# SSD1963_drier.net
KiCad netlist of a schematic drawn in EAGLE
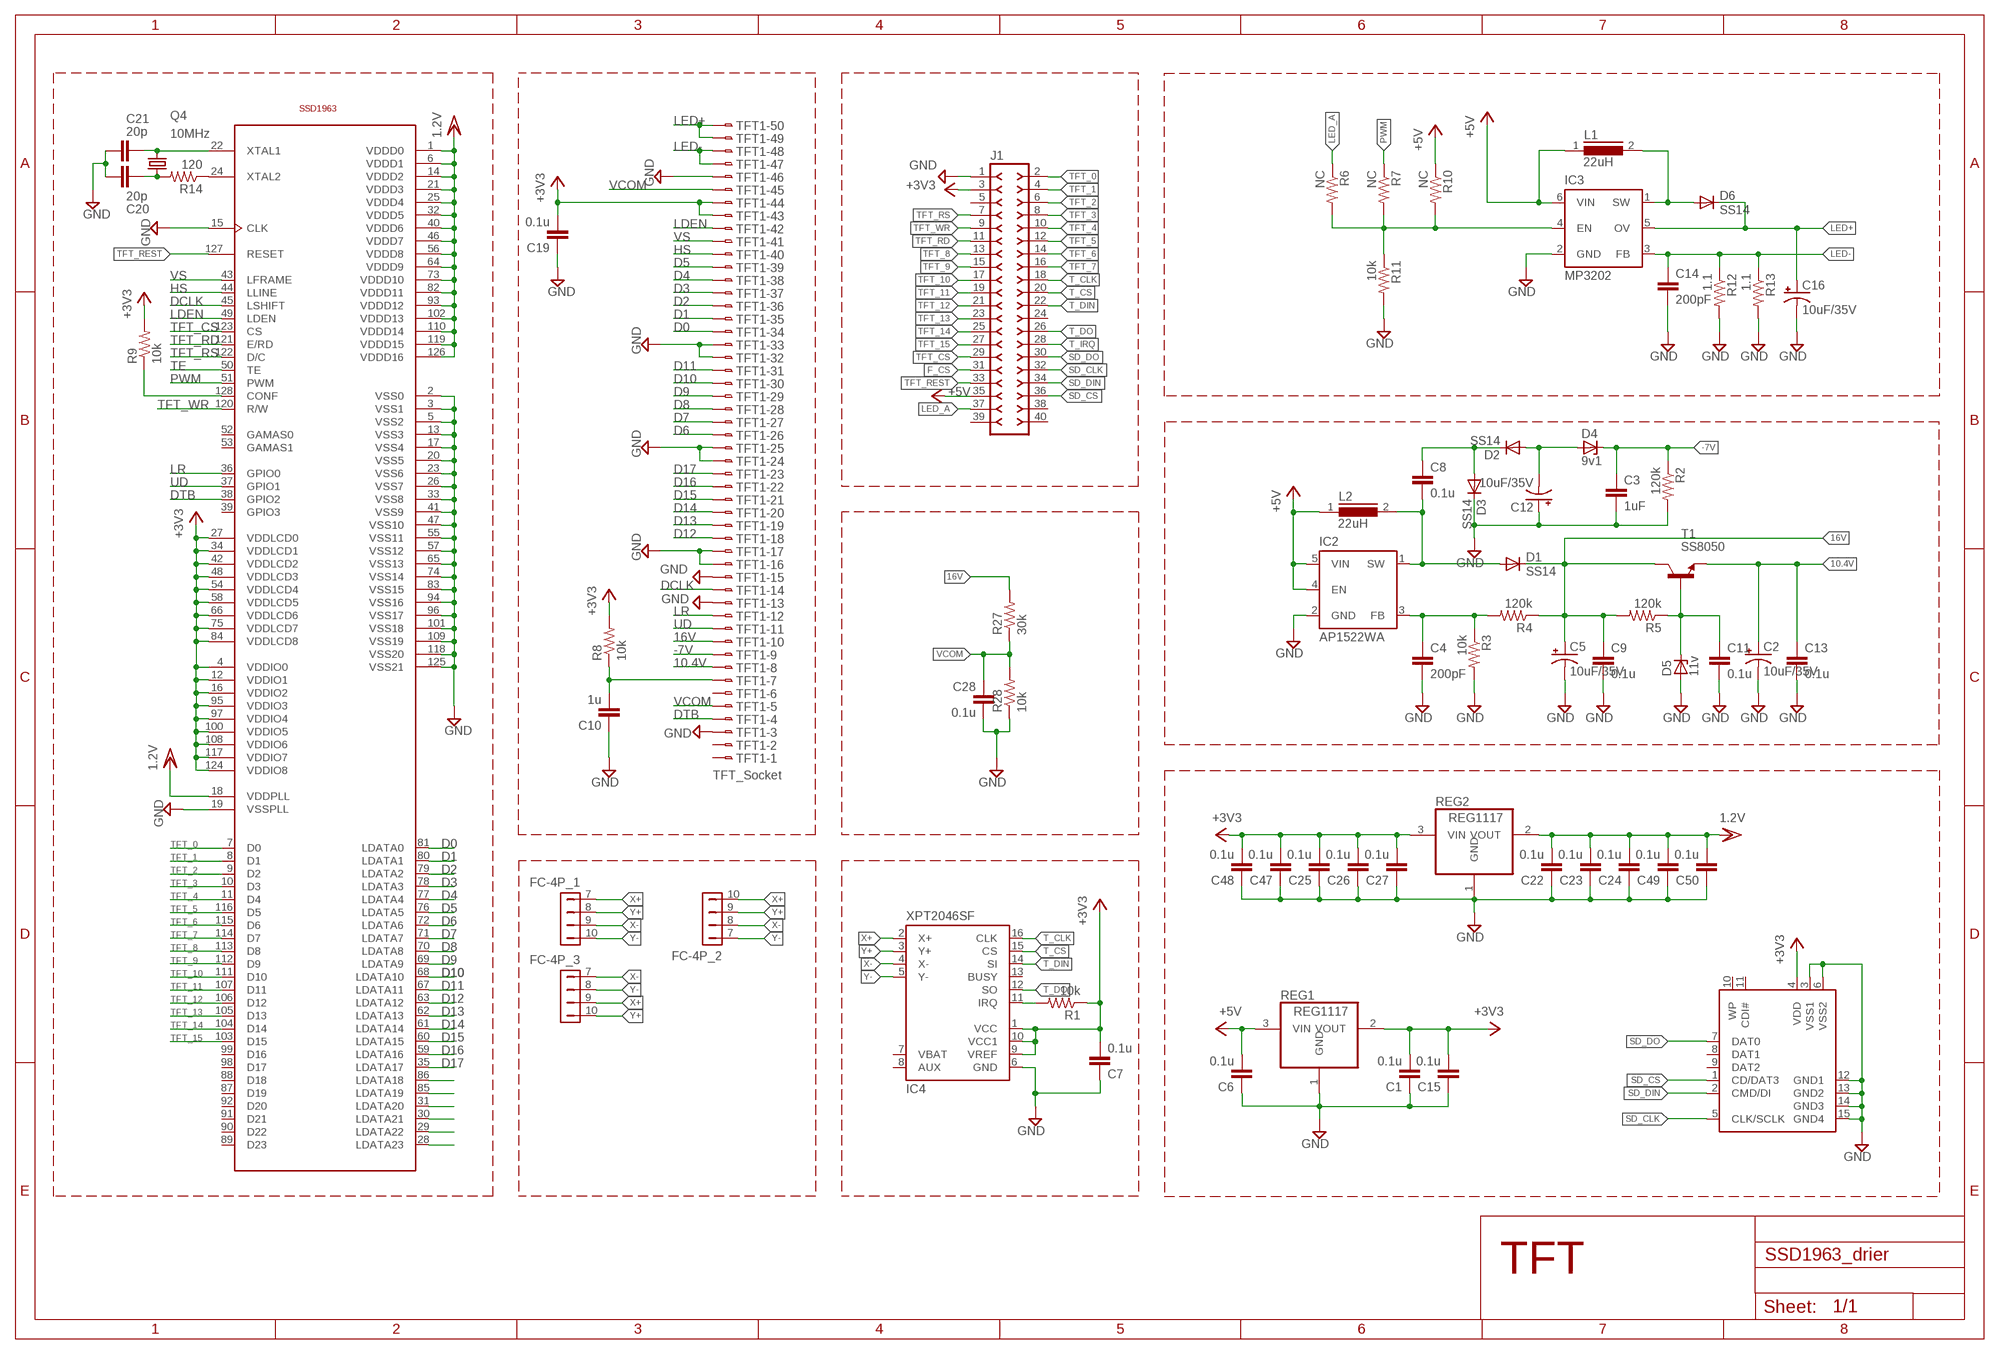
[diagram p0: schematic, sheet 1]

(export (version "E")
  (design (tool "Eeschema 10.0.6"))
  (components
    (comp (ref "C1")
      (value "0.1u")
      (footprint "eagle-import:C0805")
      (libsource (lib "eagle-import") (part "C-EUC0805"))
    )
    (comp (ref "C2")
      (value "10uF/35V")
      (footprint "eagle-import:B_3528-21R")
      (libsource (lib "eagle-import") (part "CPOL-USB/3528-21R"))
    )
    (comp (ref "C3")
      (value "1uF")
      (footprint "eagle-import:C0805")
      (libsource (lib "eagle-import") (part "C-EUC0805"))
    )
    (comp (ref "C4")
      (value "200pF")
      (footprint "eagle-import:C0805")
      (libsource (lib "eagle-import") (part "C-EUC0805"))
    )
    (comp (ref "C5")
      (value "10uF/35V")
      (footprint "eagle-import:B_3528-21R")
      (libsource (lib "eagle-import") (part "CPOL-USB/3528-21R"))
    )
    (comp (ref "C6")
      (value "0.1u")
      (footprint "eagle-import:C0805")
      (libsource (lib "eagle-import") (part "C-EUC0805"))
    )
    (comp (ref "C7")
      (value "0.1u")
      (footprint "eagle-import:C0805")
      (libsource (lib "eagle-import") (part "C-EUC0805"))
    )
    (comp (ref "C8")
      (value "0.1u")
      (footprint "eagle-import:C0805")
      (libsource (lib "eagle-import") (part "C-EUC0805"))
    )
    (comp (ref "C9")
      (value "0.1u")
      (footprint "eagle-import:C0805")
      (libsource (lib "eagle-import") (part "C-EUC0805"))
    )
    (comp (ref "C10")
      (value "1u")
      (footprint "eagle-import:C0805")
      (libsource (lib "eagle-import") (part "C-EUC0805"))
    )
    (comp (ref "C11")
      (value "0.1u")
      (footprint "eagle-import:C0805")
      (libsource (lib "eagle-import") (part "C-EUC0805"))
    )
    (comp (ref "C12")
      (value "10uF/35V")
      (footprint "eagle-import:B_3528-21R")
      (libsource (lib "eagle-import") (part "CPOL-USB/3528-21R"))
    )
    (comp (ref "C13")
      (value "0.1u")
      (footprint "eagle-import:C0805")
      (libsource (lib "eagle-import") (part "C-EUC0805"))
    )
    (comp (ref "C14")
      (value "200pF")
      (footprint "eagle-import:C0805")
      (libsource (lib "eagle-import") (part "C-EUC0805"))
    )
    (comp (ref "C15")
      (value "0.1u")
      (footprint "eagle-import:C0805")
      (libsource (lib "eagle-import") (part "C-EUC0805"))
    )
    (comp (ref "C16")
      (value "10uF/35V")
      (footprint "eagle-import:B_3528-21R")
      (libsource (lib "eagle-import") (part "CPOL-USB/3528-21R"))
    )
    (comp (ref "C19")
      (value "0.1u")
      (footprint "eagle-import:C0805")
      (libsource (lib "eagle-import") (part "C-EUC0805"))
    )
    (comp (ref "C20")
      (value "20p")
      (footprint "eagle-import:C0805")
      (libsource (lib "eagle-import") (part "C-EUC0805"))
    )
    (comp (ref "C21")
      (value "20p")
      (footprint "eagle-import:C0805")
      (libsource (lib "eagle-import") (part "C-EUC0805"))
    )
    (comp (ref "C22")
      (value "0.1u")
      (footprint "eagle-import:C0805")
      (libsource (lib "eagle-import") (part "C-EUC0805"))
    )
    (comp (ref "C23")
      (value "0.1u")
      (footprint "eagle-import:C0805")
      (libsource (lib "eagle-import") (part "C-EUC0805"))
    )
    (comp (ref "C24")
      (value "0.1u")
      (footprint "eagle-import:C0805")
      (libsource (lib "eagle-import") (part "C-EUC0805"))
    )
    (comp (ref "C25")
      (value "0.1u")
      (footprint "eagle-import:C0805")
      (libsource (lib "eagle-import") (part "C-EUC0805"))
    )
    (comp (ref "C26")
      (value "0.1u")
      (footprint "eagle-import:C0805")
      (libsource (lib "eagle-import") (part "C-EUC0805"))
    )
    (comp (ref "C27")
      (value "0.1u")
      (footprint "eagle-import:C0805")
      (libsource (lib "eagle-import") (part "C-EUC0805"))
    )
    (comp (ref "C28")
      (value "0.1u")
      (footprint "eagle-import:C0805")
      (libsource (lib "eagle-import") (part "C-EUC0805"))
    )
    (comp (ref "C47")
      (value "0.1u")
      (footprint "eagle-import:C0805")
      (libsource (lib "eagle-import") (part "C-EUC0805"))
    )
    (comp (ref "C48")
      (value "0.1u")
      (footprint "eagle-import:C0805")
      (libsource (lib "eagle-import") (part "C-EUC0805"))
    )
    (comp (ref "C49")
      (value "0.1u")
      (footprint "eagle-import:C0805")
      (libsource (lib "eagle-import") (part "C-EUC0805"))
    )
    (comp (ref "C50")
      (value "0.1u")
      (footprint "eagle-import:C0805")
      (libsource (lib "eagle-import") (part "C-EUC0805"))
    )
    (comp (ref "D1")
      (value "SS14")
      (footprint "eagle-import:DO214AC")
      (libsource (lib "eagle-import") (part "DIODE-DO214AC"))
    )
    (comp (ref "D2")
      (value "SS14")
      (footprint "eagle-import:DO214AC")
      (libsource (lib "eagle-import") (part "DIODE-DO214AC"))
    )
    (comp (ref "D3")
      (value "SS14")
      (footprint "eagle-import:DO214AC")
      (libsource (lib "eagle-import") (part "DIODE-DO214AC"))
    )
    (comp (ref "D4")
      (value "9v1")
      (footprint "eagle-import:SOD80C")
      (libsource (lib "eagle-import") (part "ZENER-DIODESOD80C"))
    )
    (comp (ref "D5")
      (value "11v")
      (footprint "eagle-import:SOD80C")
      (libsource (lib "eagle-import") (part "ZENER-DIODESOD80C"))
    )
    (comp (ref "D6")
      (value "SS14")
      (footprint "eagle-import:DO214AC")
      (libsource (lib "eagle-import") (part "DIODE-DO214AC"))
    )
    (comp (ref "FC-4P_1")
      (value "FH12-04S-1S")
      (footprint "eagle-import:FH12-4S-1SH")
      (libsource (lib "eagle-import") (part "FH12-04S-1S"))
    )
    (comp (ref "FC-4P_2")
      (value "FH12-04S-1S")
      (footprint "eagle-import:FH12-4S-1SH")
      (libsource (lib "eagle-import") (part "FH12-04S-1S"))
    )
    (comp (ref "FC-4P_3")
      (value "FH12-04S-1S")
      (footprint "eagle-import:FH12-4S-1SH")
      (libsource (lib "eagle-import") (part "FH12-04S-1S"))
    )
    (comp (ref "IC1")
      (value "SSD1963LQFP")
      (footprint "eagle-import:LQFP128")
      (libsource (lib "eagle-import") (part "SSD1963LQFP"))
    )
    (comp (ref "IC2")
      (value "AP1522WA")
      (footprint "eagle-import:SOT23-5L")
      (libsource (lib "eagle-import") (part "AP1522WA"))
    )
    (comp (ref "IC3")
      (value "MP3202")
      (footprint "eagle-import:SOT23-6L")
      (libsource (lib "eagle-import") (part "MP3202"))
    )
    (comp (ref "IC4")
      (value "XPT2046SF")
      (footprint "eagle-import:TSSOP16L")
      (libsource (lib "eagle-import") (part "XPT2046SF"))
    )
    (comp (ref "J1")
      (value "F-2X20-SF-100")
      (footprint "eagle-import:SF-100-2X20")
      (libsource (lib "eagle-import") (part "F-2X20-SF-100"))
    )
    (comp (ref "L1")
      (value "22uH")
      (footprint "eagle-import:DR74")
      (libsource (lib "eagle-import") (part "DR74"))
    )
    (comp (ref "L2")
      (value "22uH")
      (footprint "eagle-import:DR74")
      (libsource (lib "eagle-import") (part "DR74"))
    )
    (comp (ref "Q4")
      (value "10MHz")
      (footprint "eagle-import:HC49UP")
      (fields (field (name "OC_FARNELL") "unknown") (field (name "OC_NEWARK") "unknown"))
      (libsource (lib "eagle-import") (part "CRYSTALHC49UP"))
    )
    (comp (ref "R1")
      (value "10k")
      (footprint "eagle-import:R0805")
      (libsource (lib "eagle-import") (part "R-US_R0805"))
    )
    (comp (ref "R2")
      (value "120k")
      (footprint "eagle-import:R0805")
      (libsource (lib "eagle-import") (part "R-US_R0805"))
    )
    (comp (ref "R3")
      (value "10k")
      (footprint "eagle-import:R0805")
      (libsource (lib "eagle-import") (part "R-US_R0805"))
    )
    (comp (ref "R4")
      (value "120k")
      (footprint "eagle-import:R0805")
      (libsource (lib "eagle-import") (part "R-US_R0805"))
    )
    (comp (ref "R5")
      (value "120k")
      (footprint "eagle-import:R0805")
      (libsource (lib "eagle-import") (part "R-US_R0805"))
    )
    (comp (ref "R6")
      (value "NC")
      (footprint "eagle-import:R0805")
      (libsource (lib "eagle-import") (part "R-US_R0805"))
    )
    (comp (ref "R7")
      (value "NC")
      (footprint "eagle-import:R0805")
      (libsource (lib "eagle-import") (part "R-US_R0805"))
    )
    (comp (ref "R8")
      (value "10k")
      (footprint "eagle-import:M0805")
      (libsource (lib "eagle-import") (part "resistor_R-US_M0805"))
    )
    (comp (ref "R9")
      (value "10k")
      (footprint "eagle-import:M0805")
      (libsource (lib "eagle-import") (part "resistor_R-US_M0805"))
    )
    (comp (ref "R10")
      (value "NC")
      (footprint "eagle-import:R0805")
      (libsource (lib "eagle-import") (part "R-US_R0805"))
    )
    (comp (ref "R11")
      (value "10k")
      (footprint "eagle-import:R0805")
      (libsource (lib "eagle-import") (part "R-US_R0805"))
    )
    (comp (ref "R12")
      (value "1.1")
      (footprint "eagle-import:R0805")
      (libsource (lib "eagle-import") (part "R-US_R0805"))
    )
    (comp (ref "R13")
      (value "1.1")
      (footprint "eagle-import:R0805")
      (libsource (lib "eagle-import") (part "R-US_R0805"))
    )
    (comp (ref "R14")
      (value "120")
      (footprint "eagle-import:M0805")
      (libsource (lib "eagle-import") (part "resistor_R-US_M0805"))
    )
    (comp (ref "R27")
      (value "30k")
      (footprint "eagle-import:M0805")
      (libsource (lib "eagle-import") (part "resistor_R-US_M0805"))
    )
    (comp (ref "R28")
      (value "10k")
      (footprint "eagle-import:M0805")
      (libsource (lib "eagle-import") (part "resistor_R-US_M0805"))
    )
    (comp (ref "REG1")
      (value "REG1117")
      (footprint "eagle-import:SOT223")
      (fields
        (field (name "MPN") "REG1117")
        (field (name "OC_FARNELL") "1097566")
        (field (name "OC_NEWARK") "14P6981")
      )
      (libsource (lib "eagle-import") (part "REG1117"))
    )
    (comp (ref "REG2")
      (value "REG1117")
      (footprint "eagle-import:SOT223")
      (fields
        (field (name "MPN") "REG1117")
        (field (name "OC_FARNELL") "1097566")
        (field (name "OC_NEWARK") "14P6981")
      )
      (libsource (lib "eagle-import") (part "REG1117"))
    )
    (comp (ref "SOC_1")
      (value "MMC/SD")
      (footprint "eagle-import:SDCMF-10915W010")
      (libsource (lib "eagle-import") (part "SDCARDVAR2"))
    )
    (comp (ref "T1")
      (value "SS8050")
      (footprint "eagle-import:SOT23")
      (libsource (lib "eagle-import") (part "BC847"))
    )
    (comp (ref "TFT1")
      (value "TFT_Socket")
      (footprint "eagle-import:50")
      (libsource (lib "eagle-import") (part "FH28-50S-0.5SH(51)XL"))
    )
  )
  (nets
    (net (code "1") (name "+3V3") (class "Default")
      (node (ref "C1") (pin "2") (pinfunction "2_2") (pintype "passive"))
      (node (ref "C15") (pin "2") (pinfunction "2_2") (pintype "passive"))
      (node (ref "C19") (pin "2") (pinfunction "2_2") (pintype "passive"))
      (node (ref "C25") (pin "2") (pinfunction "2_2") (pintype "passive"))
      (node (ref "C26") (pin "2") (pinfunction "2_2") (pintype "passive"))
      (node (ref "C27") (pin "2") (pinfunction "2_2") (pintype "passive"))
      (node (ref "C47") (pin "2") (pinfunction "2_2") (pintype "passive"))
      (node (ref "C48") (pin "2") (pinfunction "2_2") (pintype "passive"))
      (node (ref "C7") (pin "2") (pinfunction "2_2") (pintype "passive"))
      (node (ref "IC1") (pin "100") (pinfunction "VDDIO5_100") (pintype "power_in"))
      (node (ref "IC1") (pin "108") (pinfunction "VDDIO6_108") (pintype "power_in"))
      (node (ref "IC1") (pin "117") (pinfunction "VDDIO7_117") (pintype "power_in"))
      (node (ref "IC1") (pin "12") (pinfunction "VDDIO1_12") (pintype "power_in"))
      (node (ref "IC1") (pin "124") (pinfunction "VDDIO8_124") (pintype "power_in"))
      (node (ref "IC1") (pin "16") (pinfunction "VDDIO2_16") (pintype "power_in"))
      (node (ref "IC1") (pin "27") (pinfunction "VDDLCD0_27") (pintype "power_in"))
      (node (ref "IC1") (pin "34") (pinfunction "VDDLCD1_34") (pintype "power_in"))
      (node (ref "IC1") (pin "4") (pinfunction "VDDIO0_4") (pintype "power_in"))
      (node (ref "IC1") (pin "42") (pinfunction "VDDLCD2_42") (pintype "power_in"))
      (node (ref "IC1") (pin "48") (pinfunction "VDDLCD3_48") (pintype "power_in"))
      (node (ref "IC1") (pin "54") (pinfunction "VDDLCD4_54") (pintype "power_in"))
      (node (ref "IC1") (pin "58") (pinfunction "VDDLCD5_58") (pintype "power_in"))
      (node (ref "IC1") (pin "66") (pinfunction "VDDLCD6_66") (pintype "power_in"))
      (node (ref "IC1") (pin "75") (pinfunction "VDDLCD7_75") (pintype "power_in"))
      (node (ref "IC1") (pin "84") (pinfunction "VDDLCD8_84") (pintype "power_in"))
      (node (ref "IC1") (pin "95") (pinfunction "VDDIO3_95") (pintype "power_in"))
      (node (ref "IC1") (pin "97") (pinfunction "VDDIO4_97") (pintype "power_in"))
      (node (ref "IC4") (pin "1") (pinfunction "VCC_1") (pintype "bidirectional"))
      (node (ref "IC4") (pin "10") (pinfunction "VCC1_10") (pintype "bidirectional"))
      (node (ref "IC4") (pin "9") (pinfunction "VREF_9") (pintype "bidirectional"))
      (node (ref "J1") (pin "3") (pinfunction "3_3") (pintype "passive"))
      (node (ref "R1") (pin "1") (pinfunction "1_1") (pintype "passive"))
      (node (ref "R8") (pin "2") (pinfunction "2_2") (pintype "passive"))
      (node (ref "R9") (pin "2") (pinfunction "2_2") (pintype "passive"))
      (node (ref "REG1") (pin "2") (pinfunction "VOUT_2") (pintype "output"))
      (node (ref "REG2") (pin "3") (pinfunction "VIN_3") (pintype "input"))
      (node (ref "SOC_1") (pin "4") (pinfunction "VDD_4") (pintype "power_in"))
      (node (ref "TFT1") (pin "43") (pinfunction "1_43") (pintype "passive"))
      (node (ref "TFT1") (pin "44") (pinfunction "1_44") (pintype "passive"))
    )
    (net (code "2") (name "+5V") (class "Default")
      (node (ref "C6") (pin "2") (pinfunction "2_2") (pintype "passive"))
      (node (ref "IC2") (pin "4") (pinfunction "EN_4") (pintype "bidirectional"))
      (node (ref "IC2") (pin "5") (pinfunction "VIN_5") (pintype "bidirectional"))
      (node (ref "IC3") (pin "6") (pinfunction "VIN_6") (pintype "bidirectional"))
      (node (ref "J1") (pin "35") (pinfunction "35_35") (pintype "passive"))
      (node (ref "L1") (pin "1") (pinfunction "1_1") (pintype "passive"))
      (node (ref "L2") (pin "1") (pinfunction "1_1") (pintype "passive"))
      (node (ref "R10") (pin "1") (pinfunction "1_1") (pintype "passive"))
      (node (ref "REG1") (pin "3") (pinfunction "VIN_3") (pintype "input"))
    )
    (net (code "3") (name "-7V") (class "Default")
      (node (ref "C3") (pin "1") (pinfunction "1_1") (pintype "passive"))
      (node (ref "D4") (pin "C") (pinfunction "C_C") (pintype "passive"))
      (node (ref "R2") (pin "1") (pinfunction "1_1") (pintype "passive"))
      (node (ref "TFT1") (pin "9") (pinfunction "1_9") (pintype "passive"))
    )
    (net (code "4") (name "/D0") (class "Default")
      (node (ref "IC1") (pin "81") (pinfunction "LDATA0_81") (pintype "bidirectional"))
      (node (ref "TFT1") (pin "34") (pinfunction "1_34") (pintype "passive"))
    )
    (net (code "5") (name "/D1") (class "Default")
      (node (ref "IC1") (pin "80") (pinfunction "LDATA1_80") (pintype "bidirectional"))
      (node (ref "TFT1") (pin "35") (pinfunction "1_35") (pintype "passive"))
    )
    (net (code "6") (name "/D2") (class "Default")
      (node (ref "IC1") (pin "79") (pinfunction "LDATA2_79") (pintype "bidirectional"))
      (node (ref "TFT1") (pin "36") (pinfunction "1_36") (pintype "passive"))
    )
    (net (code "7") (name "/D3") (class "Default")
      (node (ref "IC1") (pin "78") (pinfunction "LDATA3_78") (pintype "bidirectional"))
      (node (ref "TFT1") (pin "37") (pinfunction "1_37") (pintype "passive"))
    )
    (net (code "8") (name "/D4") (class "Default")
      (node (ref "IC1") (pin "77") (pinfunction "LDATA4_77") (pintype "bidirectional"))
      (node (ref "TFT1") (pin "38") (pinfunction "1_38") (pintype "passive"))
    )
    (net (code "9") (name "/D5") (class "Default")
      (node (ref "IC1") (pin "76") (pinfunction "LDATA5_76") (pintype "bidirectional"))
      (node (ref "TFT1") (pin "39") (pinfunction "1_39") (pintype "passive"))
    )
    (net (code "10") (name "/D6") (class "Default")
      (node (ref "IC1") (pin "72") (pinfunction "LDATA6_72") (pintype "bidirectional"))
      (node (ref "TFT1") (pin "26") (pinfunction "1_26") (pintype "passive"))
    )
    (net (code "11") (name "/D7") (class "Default")
      (node (ref "IC1") (pin "71") (pinfunction "LDATA7_71") (pintype "bidirectional"))
      (node (ref "TFT1") (pin "27") (pinfunction "1_27") (pintype "passive"))
    )
    (net (code "12") (name "/D8") (class "Default")
      (node (ref "IC1") (pin "70") (pinfunction "LDATA8_70") (pintype "bidirectional"))
      (node (ref "TFT1") (pin "28") (pinfunction "1_28") (pintype "passive"))
    )
    (net (code "13") (name "/D9") (class "Default")
      (node (ref "IC1") (pin "69") (pinfunction "LDATA9_69") (pintype "bidirectional"))
      (node (ref "TFT1") (pin "29") (pinfunction "1_29") (pintype "passive"))
    )
    (net (code "14") (name "/D10") (class "Default")
      (node (ref "IC1") (pin "68") (pinfunction "LDATA10_68") (pintype "bidirectional"))
      (node (ref "TFT1") (pin "30") (pinfunction "1_30") (pintype "passive"))
    )
    (net (code "15") (name "/D11") (class "Default")
      (node (ref "IC1") (pin "67") (pinfunction "LDATA11_67") (pintype "bidirectional"))
      (node (ref "TFT1") (pin "31") (pinfunction "1_31") (pintype "passive"))
    )
    (net (code "16") (name "/D12") (class "Default")
      (node (ref "IC1") (pin "63") (pinfunction "LDATA12_63") (pintype "bidirectional"))
      (node (ref "TFT1") (pin "18") (pinfunction "1_18") (pintype "passive"))
    )
    (net (code "17") (name "/D13") (class "Default")
      (node (ref "IC1") (pin "62") (pinfunction "LDATA13_62") (pintype "bidirectional"))
      (node (ref "TFT1") (pin "19") (pinfunction "1_19") (pintype "passive"))
    )
    (net (code "18") (name "/D14") (class "Default")
      (node (ref "IC1") (pin "61") (pinfunction "LDATA14_61") (pintype "bidirectional"))
      (node (ref "TFT1") (pin "20") (pinfunction "1_20") (pintype "passive"))
    )
    (net (code "19") (name "/D15") (class "Default")
      (node (ref "IC1") (pin "60") (pinfunction "LDATA15_60") (pintype "bidirectional"))
      (node (ref "TFT1") (pin "21") (pinfunction "1_21") (pintype "passive"))
    )
    (net (code "20") (name "/D16") (class "Default")
      (node (ref "IC1") (pin "59") (pinfunction "LDATA16_59") (pintype "bidirectional"))
      (node (ref "TFT1") (pin "22") (pinfunction "1_22") (pintype "passive"))
    )
    (net (code "21") (name "/D17") (class "Default")
      (node (ref "IC1") (pin "35") (pinfunction "LDATA17_35") (pintype "bidirectional"))
      (node (ref "TFT1") (pin "23") (pinfunction "1_23") (pintype "passive"))
    )
    (net (code "22") (name "/DCLK") (class "Default")
      (node (ref "IC1") (pin "45") (pinfunction "LSHIFT_45") (pintype "bidirectional"))
      (node (ref "TFT1") (pin "14") (pinfunction "1_14") (pintype "passive"))
    )
    (net (code "23") (name "/DTB") (class "Default")
      (node (ref "IC1") (pin "38") (pinfunction "GPIO2_38") (pintype "bidirectional"))
      (node (ref "TFT1") (pin "4") (pinfunction "1_4") (pintype "passive"))
    )
    (net (code "24") (name "/HS") (class "Default")
      (node (ref "IC1") (pin "44") (pinfunction "LLINE_44") (pintype "bidirectional"))
      (node (ref "TFT1") (pin "40") (pinfunction "1_40") (pintype "passive"))
    )
    (net (code "25") (name "/LDEN") (class "Default")
      (node (ref "IC1") (pin "49") (pinfunction "LDEN_49") (pintype "bidirectional"))
      (node (ref "TFT1") (pin "42") (pinfunction "1_42") (pintype "passive"))
    )
    (net (code "26") (name "/LR") (class "Default")
      (node (ref "IC1") (pin "36") (pinfunction "GPIO0_36") (pintype "bidirectional"))
      (node (ref "TFT1") (pin "12") (pinfunction "1_12") (pintype "passive"))
    )
    (net (code "27") (name "/TE") (class "Default")
      (node (ref "IC1") (pin "50") (pinfunction "TE_50") (pintype "bidirectional"))
    )
    (net (code "28") (name "/UD") (class "Default")
      (node (ref "IC1") (pin "37") (pinfunction "GPIO1_37") (pintype "bidirectional"))
      (node (ref "TFT1") (pin "11") (pinfunction "1_11") (pintype "passive"))
    )
    (net (code "29") (name "/VS") (class "Default")
      (node (ref "IC1") (pin "43") (pinfunction "LFRAME_43") (pintype "bidirectional"))
      (node (ref "TFT1") (pin "41") (pinfunction "1_41") (pintype "passive"))
    )
    (net (code "30") (name "1.2V") (class "Default")
      (node (ref "C22") (pin "2") (pinfunction "2_2") (pintype "passive"))
      (node (ref "C23") (pin "2") (pinfunction "2_2") (pintype "passive"))
      (node (ref "C24") (pin "2") (pinfunction "2_2") (pintype "passive"))
      (node (ref "C49") (pin "2") (pinfunction "2_2") (pintype "passive"))
      (node (ref "C50") (pin "2") (pinfunction "2_2") (pintype "passive"))
      (node (ref "IC1") (pin "1") (pinfunction "VDDD0_1") (pintype "power_in"))
      (node (ref "IC1") (pin "102") (pinfunction "VDDD13_102") (pintype "power_in"))
      (node (ref "IC1") (pin "110") (pinfunction "VDDD14_110") (pintype "power_in"))
      (node (ref "IC1") (pin "119") (pinfunction "VDDD15_119") (pintype "power_in"))
      (node (ref "IC1") (pin "126") (pinfunction "VDDD16_126") (pintype "power_in"))
      (node (ref "IC1") (pin "14") (pinfunction "VDDD2_14") (pintype "power_in"))
      (node (ref "IC1") (pin "18") (pinfunction "VDDPLL_18") (pintype "power_in"))
      (node (ref "IC1") (pin "21") (pinfunction "VDDD3_21") (pintype "power_in"))
      (node (ref "IC1") (pin "25") (pinfunction "VDDD4_25") (pintype "power_in"))
      (node (ref "IC1") (pin "32") (pinfunction "VDDD5_32") (pintype "power_in"))
      (node (ref "IC1") (pin "40") (pinfunction "VDDD6_40") (pintype "power_in"))
      (node (ref "IC1") (pin "46") (pinfunction "VDDD7_46") (pintype "power_in"))
      (node (ref "IC1") (pin "56") (pinfunction "VDDD8_56") (pintype "power_in"))
      (node (ref "IC1") (pin "6") (pinfunction "VDDD1_6") (pintype "power_in"))
      (node (ref "IC1") (pin "64") (pinfunction "VDDD9_64") (pintype "power_in"))
      (node (ref "IC1") (pin "73") (pinfunction "VDDD10_73") (pintype "power_in"))
      (node (ref "IC1") (pin "82") (pinfunction "VDDD11_82") (pintype "power_in"))
      (node (ref "IC1") (pin "93") (pinfunction "VDDD12_93") (pintype "power_in"))
      (node (ref "REG2") (pin "2") (pinfunction "VOUT_2") (pintype "output"))
    )
    (net (code "31") (name "10.4V") (class "Default")
      (node (ref "C13") (pin "1") (pinfunction "1_1") (pintype "passive"))
      (node (ref "C2") (pin "+") (pinfunction "+_+") (pintype "passive"))
      (node (ref "T1") (pin "2") (pinfunction "E_2") (pintype "passive"))
      (node (ref "TFT1") (pin "8") (pinfunction "1_8") (pintype "passive"))
    )
    (net (code "32") (name "16V") (class "Default")
      (node (ref "C5") (pin "+") (pinfunction "+_+") (pintype "passive"))
      (node (ref "C9") (pin "1") (pinfunction "1_1") (pintype "passive"))
      (node (ref "D1") (pin "C") (pinfunction "C_C") (pintype "passive"))
      (node (ref "R27") (pin "2") (pinfunction "2_2") (pintype "passive"))
      (node (ref "R4") (pin "1") (pinfunction "1_1") (pintype "passive"))
      (node (ref "R5") (pin "2") (pinfunction "2_2") (pintype "passive"))
      (node (ref "T1") (pin "3") (pinfunction "C_3") (pintype "passive"))
      (node (ref "TFT1") (pin "10") (pinfunction "1_10") (pintype "passive"))
    )
    (net (code "33") (name "F_CS") (class "Default")
      (node (ref "J1") (pin "31") (pinfunction "31_31") (pintype "passive"))
    )
    (net (code "34") (name "GND") (class "Default")
      (node (ref "C1") (pin "1") (pinfunction "1_1") (pintype "passive"))
      (node (ref "C10") (pin "1") (pinfunction "1_1") (pintype "passive"))
      (node (ref "C11") (pin "2") (pinfunction "2_2") (pintype "passive"))
      (node (ref "C12") (pin "+") (pinfunction "+_+") (pintype "passive"))
      (node (ref "C13") (pin "2") (pinfunction "2_2") (pintype "passive"))
      (node (ref "C14") (pin "2") (pinfunction "2_2") (pintype "passive"))
      (node (ref "C15") (pin "1") (pinfunction "1_1") (pintype "passive"))
      (node (ref "C16") (pin "-") (pinfunction "-_-") (pintype "passive"))
      (node (ref "C19") (pin "1") (pinfunction "1_1") (pintype "passive"))
      (node (ref "C2") (pin "-") (pinfunction "-_-") (pintype "passive"))
      (node (ref "C20") (pin "1") (pinfunction "1_1") (pintype "passive"))
      (node (ref "C21") (pin "1") (pinfunction "1_1") (pintype "passive"))
      (node (ref "C22") (pin "1") (pinfunction "1_1") (pintype "passive"))
      (node (ref "C23") (pin "1") (pinfunction "1_1") (pintype "passive"))
      (node (ref "C24") (pin "1") (pinfunction "1_1") (pintype "passive"))
      (node (ref "C25") (pin "1") (pinfunction "1_1") (pintype "passive"))
      (node (ref "C26") (pin "1") (pinfunction "1_1") (pintype "passive"))
      (node (ref "C27") (pin "1") (pinfunction "1_1") (pintype "passive"))
      (node (ref "C28") (pin "2") (pinfunction "2_2") (pintype "passive"))
      (node (ref "C3") (pin "2") (pinfunction "2_2") (pintype "passive"))
      (node (ref "C4") (pin "2") (pinfunction "2_2") (pintype "passive"))
      (node (ref "C47") (pin "1") (pinfunction "1_1") (pintype "passive"))
      (node (ref "C48") (pin "1") (pinfunction "1_1") (pintype "passive"))
      (node (ref "C49") (pin "1") (pinfunction "1_1") (pintype "passive"))
      (node (ref "C5") (pin "-") (pinfunction "-_-") (pintype "passive"))
      (node (ref "C50") (pin "1") (pinfunction "1_1") (pintype "passive"))
      (node (ref "C6") (pin "1") (pinfunction "1_1") (pintype "passive"))
      (node (ref "C7") (pin "1") (pinfunction "1_1") (pintype "passive"))
      (node (ref "C9") (pin "2") (pinfunction "2_2") (pintype "passive"))
      (node (ref "D3") (pin "C") (pinfunction "C_C") (pintype "passive"))
      (node (ref "D5") (pin "A") (pinfunction "A_A") (pintype "passive"))
      (node (ref "IC1") (pin "101") (pinfunction "VSS18_101") (pintype "power_in"))
      (node (ref "IC1") (pin "109") (pinfunction "VSS19_109") (pintype "power_in"))
      (node (ref "IC1") (pin "118") (pinfunction "VSS20_118") (pintype "power_in"))
      (node (ref "IC1") (pin "125") (pinfunction "VSS21_125") (pintype "power_in"))
      (node (ref "IC1") (pin "13") (pinfunction "VSS3_13") (pintype "power_in"))
      (node (ref "IC1") (pin "15") (pinfunction "CLK_15") (pintype "open_collector"))
      (node (ref "IC1") (pin "17") (pinfunction "VSS4_17") (pintype "power_in"))
      (node (ref "IC1") (pin "19") (pinfunction "VSSPLL_19") (pintype "power_in"))
      (node (ref "IC1") (pin "2") (pinfunction "VSS0_2") (pintype "power_in"))
      (node (ref "IC1") (pin "20") (pinfunction "VSS5_20") (pintype "power_in"))
      (node (ref "IC1") (pin "23") (pinfunction "VSS6_23") (pintype "power_in"))
      (node (ref "IC1") (pin "26") (pinfunction "VSS7_26") (pintype "power_in"))
      (node (ref "IC1") (pin "3") (pinfunction "VSS1_3") (pintype "power_in"))
      (node (ref "IC1") (pin "33") (pinfunction "VSS8_33") (pintype "power_in"))
      (node (ref "IC1") (pin "41") (pinfunction "VSS9_41") (pintype "power_in"))
      (node (ref "IC1") (pin "47") (pinfunction "VSS10_47") (pintype "power_in"))
      (node (ref "IC1") (pin "5") (pinfunction "VSS2_5") (pintype "power_in"))
      (node (ref "IC1") (pin "55") (pinfunction "VSS11_55") (pintype "power_in"))
      (node (ref "IC1") (pin "57") (pinfunction "VSS12_57") (pintype "power_in"))
      (node (ref "IC1") (pin "65") (pinfunction "VSS13_65") (pintype "power_in"))
      (node (ref "IC1") (pin "74") (pinfunction "VSS14_74") (pintype "power_in"))
      (node (ref "IC1") (pin "83") (pinfunction "VSS15_83") (pintype "power_in"))
      (node (ref "IC1") (pin "94") (pinfunction "VSS16_94") (pintype "power_in"))
      (node (ref "IC1") (pin "96") (pinfunction "VSS17_96") (pintype "power_in"))
      (node (ref "IC2") (pin "2") (pinfunction "GND_2") (pintype "bidirectional"))
      (node (ref "IC3") (pin "2") (pinfunction "GND_2") (pintype "bidirectional"))
      (node (ref "IC4") (pin "6") (pinfunction "GND_6") (pintype "bidirectional"))
      (node (ref "J1") (pin "1") (pinfunction "1_1") (pintype "passive"))
      (node (ref "R11") (pin "2") (pinfunction "2_2") (pintype "passive"))
      (node (ref "R12") (pin "2") (pinfunction "2_2") (pintype "passive"))
      (node (ref "R13") (pin "2") (pinfunction "2_2") (pintype "passive"))
      (node (ref "R2") (pin "2") (pinfunction "2_2") (pintype "passive"))
      (node (ref "R28") (pin "1") (pinfunction "1_1") (pintype "passive"))
      (node (ref "R3") (pin "2") (pinfunction "2_2") (pintype "passive"))
      (node (ref "REG1") (pin "1") (pinfunction "GND_1") (pintype "power_in"))
      (node (ref "REG2") (pin "1") (pinfunction "GND_1") (pintype "power_in"))
      (node (ref "SOC_1") (pin "12") (pinfunction "GND1_12") (pintype "power_in"))
      (node (ref "SOC_1") (pin "13") (pinfunction "GND2_13") (pintype "power_in"))
      (node (ref "SOC_1") (pin "14") (pinfunction "GND3_14") (pintype "power_in"))
      (node (ref "SOC_1") (pin "15") (pinfunction "GND4_15") (pintype "power_in"))
      (node (ref "SOC_1") (pin "3") (pinfunction "VSS1_3") (pintype "power_in"))
      (node (ref "SOC_1") (pin "6") (pinfunction "VSS2_6") (pintype "power_in"))
      (node (ref "TFT1") (pin "13") (pinfunction "1_13") (pintype "passive"))
      (node (ref "TFT1") (pin "15") (pinfunction "1_15") (pintype "passive"))
      (node (ref "TFT1") (pin "16") (pinfunction "1_16") (pintype "passive"))
      (node (ref "TFT1") (pin "17") (pinfunction "1_17") (pintype "passive"))
      (node (ref "TFT1") (pin "24") (pinfunction "1_24") (pintype "passive"))
      (node (ref "TFT1") (pin "25") (pinfunction "1_25") (pintype "passive"))
      (node (ref "TFT1") (pin "3") (pinfunction "1_3") (pintype "passive"))
      (node (ref "TFT1") (pin "32") (pinfunction "1_32") (pintype "passive"))
      (node (ref "TFT1") (pin "33") (pinfunction "1_33") (pintype "passive"))
      (node (ref "TFT1") (pin "46") (pinfunction "1_46") (pintype "passive"))
    )
    (net (code "35") (name "LED+") (class "Default")
      (node (ref "C16") (pin "+") (pinfunction "+_+") (pintype "passive"))
      (node (ref "D6") (pin "C") (pinfunction "C_C") (pintype "passive"))
      (node (ref "IC3") (pin "5") (pinfunction "OV_5") (pintype "bidirectional"))
      (node (ref "TFT1") (pin "49") (pinfunction "1_49") (pintype "passive"))
      (node (ref "TFT1") (pin "50") (pinfunction "1_50") (pintype "passive"))
    )
    (net (code "36") (name "LED-") (class "Default")
      (node (ref "C14") (pin "1") (pinfunction "1_1") (pintype "passive"))
      (node (ref "IC3") (pin "3") (pinfunction "FB_3") (pintype "bidirectional"))
      (node (ref "R12") (pin "1") (pinfunction "1_1") (pintype "passive"))
      (node (ref "R13") (pin "1") (pinfunction "1_1") (pintype "passive"))
      (node (ref "TFT1") (pin "47") (pinfunction "1_47") (pintype "passive"))
      (node (ref "TFT1") (pin "48") (pinfunction "1_48") (pintype "passive"))
    )
    (net (code "37") (name "LED_A") (class "Default")
      (node (ref "J1") (pin "37") (pinfunction "37_37") (pintype "passive"))
      (node (ref "R6") (pin "1") (pinfunction "1_1") (pintype "passive"))
    )
    (net (code "38") (name "Net-(C8-Pad1)") (class "Default")
      (node (ref "C8") (pin "1") (pinfunction "1_1") (pintype "passive"))
      (node (ref "D2") (pin "C") (pinfunction "C_C") (pintype "passive"))
      (node (ref "D3") (pin "A") (pinfunction "A_A") (pintype "passive"))
    )
    (net (code "39") (name "Net-(C12-Pad-)") (class "Default")
      (node (ref "C12") (pin "-") (pinfunction "-_-") (pintype "passive"))
      (node (ref "D2") (pin "A") (pinfunction "A_A") (pintype "passive"))
      (node (ref "D4") (pin "A") (pinfunction "A_A") (pintype "passive"))
    )
    (net (code "40") (name "Net-(C20-Pad2)") (class "Default")
      (node (ref "C20") (pin "2") (pinfunction "2_2") (pintype "passive"))
      (node (ref "Q4") (pin "1") (pinfunction "1_1") (pintype "passive"))
      (node (ref "R14") (pin "2") (pinfunction "2_2") (pintype "passive"))
    )
    (net (code "41") (name "Net-(IC1-CONF)") (class "Default")
      (node (ref "IC1") (pin "128") (pinfunction "CONF_128") (pintype "bidirectional"))
      (node (ref "R9") (pin "1") (pinfunction "1_1") (pintype "passive"))
    )
    (net (code "42") (name "Net-(IC1-XTAL1)") (class "Default")
      (node (ref "C21") (pin "2") (pinfunction "2_2") (pintype "passive"))
      (node (ref "IC1") (pin "22") (pinfunction "XTAL1_22") (pintype "open_collector"))
      (node (ref "Q4") (pin "2") (pinfunction "2_2") (pintype "passive"))
    )
    (net (code "43") (name "Net-(IC1-XTAL2)") (class "Default")
      (node (ref "IC1") (pin "24") (pinfunction "XTAL2_24") (pintype "open_collector"))
      (node (ref "R14") (pin "1") (pinfunction "1_1") (pintype "passive"))
    )
    (net (code "44") (name "Net-(IC2-FB)") (class "Default")
      (node (ref "C4") (pin "1") (pinfunction "1_1") (pintype "passive"))
      (node (ref "IC2") (pin "3") (pinfunction "FB_3") (pintype "bidirectional"))
      (node (ref "R3") (pin "1") (pinfunction "1_1") (pintype "passive"))
      (node (ref "R4") (pin "2") (pinfunction "2_2") (pintype "passive"))
    )
    (net (code "45") (name "Net-(IC2-SW)") (class "Default")
      (node (ref "C8") (pin "2") (pinfunction "2_2") (pintype "passive"))
      (node (ref "D1") (pin "A") (pinfunction "A_A") (pintype "passive"))
      (node (ref "IC2") (pin "1") (pinfunction "SW_1") (pintype "bidirectional"))
      (node (ref "L2") (pin "2") (pinfunction "2_2") (pintype "passive"))
    )
    (net (code "46") (name "Net-(IC3-EN)") (class "Default")
      (node (ref "IC3") (pin "4") (pinfunction "EN_4") (pintype "bidirectional"))
      (node (ref "R10") (pin "2") (pinfunction "2_2") (pintype "passive"))
      (node (ref "R11") (pin "1") (pinfunction "1_1") (pintype "passive"))
      (node (ref "R6") (pin "2") (pinfunction "2_2") (pintype "passive"))
      (node (ref "R7") (pin "2") (pinfunction "2_2") (pintype "passive"))
    )
    (net (code "47") (name "Net-(IC3-SW)") (class "Default")
      (node (ref "D6") (pin "A") (pinfunction "A_A") (pintype "passive"))
      (node (ref "IC3") (pin "1") (pinfunction "SW_1") (pintype "bidirectional"))
      (node (ref "L1") (pin "2") (pinfunction "2_2") (pintype "passive"))
    )
    (net (code "48") (name "Net-(T1-B)") (class "Default")
      (node (ref "C11") (pin "1") (pinfunction "1_1") (pintype "passive"))
      (node (ref "D5") (pin "C") (pinfunction "C_C") (pintype "passive"))
      (node (ref "R5") (pin "1") (pinfunction "1_1") (pintype "passive"))
      (node (ref "T1") (pin "1") (pinfunction "B_1") (pintype "passive"))
    )
    (net (code "49") (name "Net-(TFT1AV-1)") (class "Default")
      (node (ref "C10") (pin "2") (pinfunction "2_2") (pintype "passive"))
      (node (ref "R8") (pin "1") (pinfunction "1_1") (pintype "passive"))
      (node (ref "TFT1") (pin "7") (pinfunction "1_7") (pintype "passive"))
    )
    (net (code "50") (name "PWM") (class "Default")
      (node (ref "IC1") (pin "51") (pinfunction "PWM_51") (pintype "bidirectional"))
      (node (ref "R7") (pin "1") (pinfunction "1_1") (pintype "passive"))
    )
    (net (code "51") (name "SD_CLK") (class "Default")
      (node (ref "J1") (pin "32") (pinfunction "32_32") (pintype "passive"))
      (node (ref "SOC_1") (pin "5") (pinfunction "CLK/SCLK_5") (pintype "bidirectional"))
    )
    (net (code "52") (name "SD_CS") (class "Default")
      (node (ref "J1") (pin "36") (pinfunction "36_36") (pintype "passive"))
      (node (ref "SOC_1") (pin "1") (pinfunction "CD/DAT3_1") (pintype "bidirectional"))
    )
    (net (code "53") (name "SD_DIN") (class "Default")
      (node (ref "J1") (pin "34") (pinfunction "34_34") (pintype "passive"))
      (node (ref "SOC_1") (pin "2") (pinfunction "CMD/DI_2") (pintype "bidirectional"))
    )
    (net (code "54") (name "SD_DO") (class "Default")
      (node (ref "J1") (pin "30") (pinfunction "30_30") (pintype "passive"))
      (node (ref "SOC_1") (pin "7") (pinfunction "DAT0_7") (pintype "bidirectional"))
    )
    (net (code "55") (name "TFT_0") (class "Default")
      (node (ref "IC1") (pin "7") (pinfunction "D0_7") (pintype "bidirectional"))
      (node (ref "J1") (pin "2") (pinfunction "2_2") (pintype "passive"))
    )
    (net (code "56") (name "TFT_1") (class "Default")
      (node (ref "IC1") (pin "8") (pinfunction "D1_8") (pintype "bidirectional"))
      (node (ref "J1") (pin "4") (pinfunction "4_4") (pintype "passive"))
    )
    (net (code "57") (name "TFT_2") (class "Default")
      (node (ref "IC1") (pin "9") (pinfunction "D2_9") (pintype "bidirectional"))
      (node (ref "J1") (pin "6") (pinfunction "6_6") (pintype "passive"))
    )
    (net (code "58") (name "TFT_3") (class "Default")
      (node (ref "IC1") (pin "10") (pinfunction "D3_10") (pintype "bidirectional"))
      (node (ref "J1") (pin "8") (pinfunction "8_8") (pintype "passive"))
    )
    (net (code "59") (name "TFT_4") (class "Default")
      (node (ref "IC1") (pin "11") (pinfunction "D4_11") (pintype "bidirectional"))
      (node (ref "J1") (pin "10") (pinfunction "10_10") (pintype "passive"))
    )
    (net (code "60") (name "TFT_5") (class "Default")
      (node (ref "IC1") (pin "116") (pinfunction "D5_116") (pintype "bidirectional"))
      (node (ref "J1") (pin "12") (pinfunction "12_12") (pintype "passive"))
    )
    (net (code "61") (name "TFT_6") (class "Default")
      (node (ref "IC1") (pin "115") (pinfunction "D6_115") (pintype "bidirectional"))
      (node (ref "J1") (pin "14") (pinfunction "14_14") (pintype "passive"))
    )
    (net (code "62") (name "TFT_7") (class "Default")
      (node (ref "IC1") (pin "114") (pinfunction "D7_114") (pintype "bidirectional"))
      (node (ref "J1") (pin "16") (pinfunction "16_16") (pintype "passive"))
    )
    (net (code "63") (name "TFT_8") (class "Default")
      (node (ref "IC1") (pin "113") (pinfunction "D8_113") (pintype "bidirectional"))
      (node (ref "J1") (pin "13") (pinfunction "13_13") (pintype "passive"))
    )
    (net (code "64") (name "TFT_9") (class "Default")
      (node (ref "IC1") (pin "112") (pinfunction "D9_112") (pintype "bidirectional"))
      (node (ref "J1") (pin "15") (pinfunction "15_15") (pintype "passive"))
    )
    (net (code "65") (name "TFT_10") (class "Default")
      (node (ref "IC1") (pin "111") (pinfunction "D10_111") (pintype "bidirectional"))
      (node (ref "J1") (pin "17") (pinfunction "17_17") (pintype "passive"))
    )
    (net (code "66") (name "TFT_11") (class "Default")
      (node (ref "IC1") (pin "107") (pinfunction "D11_107") (pintype "bidirectional"))
      (node (ref "J1") (pin "19") (pinfunction "19_19") (pintype "passive"))
    )
    (net (code "67") (name "TFT_12") (class "Default")
      (node (ref "IC1") (pin "106") (pinfunction "D12_106") (pintype "bidirectional"))
      (node (ref "J1") (pin "21") (pinfunction "21_21") (pintype "passive"))
    )
    (net (code "68") (name "TFT_13") (class "Default")
      (node (ref "IC1") (pin "105") (pinfunction "D13_105") (pintype "bidirectional"))
      (node (ref "J1") (pin "23") (pinfunction "23_23") (pintype "passive"))
    )
    (net (code "69") (name "TFT_14") (class "Default")
      (node (ref "IC1") (pin "104") (pinfunction "D14_104") (pintype "bidirectional"))
      (node (ref "J1") (pin "25") (pinfunction "25_25") (pintype "passive"))
    )
    (net (code "70") (name "TFT_15") (class "Default")
      (node (ref "IC1") (pin "103") (pinfunction "D15_103") (pintype "bidirectional"))
      (node (ref "J1") (pin "27") (pinfunction "27_27") (pintype "passive"))
    )
    (net (code "71") (name "TFT_CS") (class "Default")
      (node (ref "IC1") (pin "123") (pinfunction "CS_123") (pintype "bidirectional"))
      (node (ref "J1") (pin "29") (pinfunction "29_29") (pintype "passive"))
    )
    (net (code "72") (name "TFT_RD") (class "Default")
      (node (ref "IC1") (pin "121") (pinfunction "E/RD_121") (pintype "bidirectional"))
      (node (ref "J1") (pin "11") (pinfunction "11_11") (pintype "passive"))
    )
    (net (code "73") (name "TFT_REST") (class "Default")
      (node (ref "IC1") (pin "127") (pinfunction "RESET_127") (pintype "input"))
      (node (ref "J1") (pin "33") (pinfunction "33_33") (pintype "passive"))
    )
    (net (code "74") (name "TFT_RS") (class "Default")
      (node (ref "IC1") (pin "122") (pinfunction "D/C_122") (pintype "bidirectional"))
      (node (ref "J1") (pin "7") (pinfunction "7_7") (pintype "passive"))
    )
    (net (code "75") (name "TFT_WR") (class "Default")
      (node (ref "IC1") (pin "120") (pinfunction "R/W_120") (pintype "bidirectional"))
      (node (ref "J1") (pin "9") (pinfunction "9_9") (pintype "passive"))
    )
    (net (code "76") (name "T_CLK") (class "Default")
      (node (ref "IC4") (pin "16") (pinfunction "CLK_16") (pintype "bidirectional"))
      (node (ref "J1") (pin "18") (pinfunction "18_18") (pintype "passive"))
    )
    (net (code "77") (name "T_CS") (class "Default")
      (node (ref "IC4") (pin "15") (pinfunction "CS_15") (pintype "bidirectional"))
      (node (ref "J1") (pin "20") (pinfunction "20_20") (pintype "passive"))
    )
    (net (code "78") (name "T_DIN") (class "Default")
      (node (ref "IC4") (pin "14") (pinfunction "SI_14") (pintype "bidirectional"))
      (node (ref "J1") (pin "22") (pinfunction "22_22") (pintype "passive"))
    )
    (net (code "79") (name "T_DO") (class "Default")
      (node (ref "IC4") (pin "12") (pinfunction "SO_12") (pintype "bidirectional"))
      (node (ref "J1") (pin "26") (pinfunction "26_26") (pintype "passive"))
    )
    (net (code "80") (name "T_IRQ") (class "Default")
      (node (ref "IC4") (pin "11") (pinfunction "IRQ_11") (pintype "bidirectional"))
      (node (ref "J1") (pin "28") (pinfunction "28_28") (pintype "passive"))
      (node (ref "R1") (pin "2") (pinfunction "2_2") (pintype "passive"))
    )
    (net (code "81") (name "VCOM") (class "Default")
      (node (ref "C28") (pin "1") (pinfunction "1_1") (pintype "passive"))
      (node (ref "R27") (pin "1") (pinfunction "1_1") (pintype "passive"))
      (node (ref "R28") (pin "2") (pinfunction "2_2") (pintype "passive"))
      (node (ref "TFT1") (pin "45") (pinfunction "1_45") (pintype "passive"))
      (node (ref "TFT1") (pin "5") (pinfunction "1_5") (pintype "passive"))
    )
    (net (code "82") (name "X+") (class "Default")
      (node (ref "FC-4P_1") (pin "7") (pinfunction "1_7") (pintype "passive"))
      (node (ref "FC-4P_2") (pin "10") (pinfunction "4_10") (pintype "passive"))
      (node (ref "FC-4P_3") (pin "9") (pinfunction "3_9") (pintype "passive"))
      (node (ref "IC4") (pin "2") (pinfunction "X+_2") (pintype "bidirectional"))
    )
    (net (code "83") (name "X-") (class "Default")
      (node (ref "FC-4P_1") (pin "9") (pinfunction "3_9") (pintype "passive"))
      (node (ref "FC-4P_2") (pin "8") (pinfunction "2_8") (pintype "passive"))
      (node (ref "FC-4P_3") (pin "7") (pinfunction "1_7") (pintype "passive"))
      (node (ref "IC4") (pin "4") (pinfunction "X-_4") (pintype "bidirectional"))
    )
    (net (code "84") (name "Y+") (class "Default")
      (node (ref "FC-4P_1") (pin "8") (pinfunction "2_8") (pintype "passive"))
      (node (ref "FC-4P_2") (pin "9") (pinfunction "3_9") (pintype "passive"))
      (node (ref "FC-4P_3") (pin "10") (pinfunction "4_10") (pintype "passive"))
      (node (ref "IC4") (pin "3") (pinfunction "Y+_3") (pintype "bidirectional"))
    )
    (net (code "85") (name "Y-") (class "Default")
      (node (ref "FC-4P_1") (pin "10") (pinfunction "4_10") (pintype "passive"))
      (node (ref "FC-4P_2") (pin "7") (pinfunction "1_7") (pintype "passive"))
      (node (ref "FC-4P_3") (pin "8") (pinfunction "2_8") (pintype "passive"))
      (node (ref "IC4") (pin "5") (pinfunction "Y-_5") (pintype "bidirectional"))
    )
    (net (code "86") (name "unconnected-(IC1-D16-Pad99)") (class "Default")
      (node (ref "IC1") (pin "99") (pinfunction "D16_99") (pintype "bidirectional"))
    )
    (net (code "87") (name "unconnected-(IC1-D17-Pad98)") (class "Default")
      (node (ref "IC1") (pin "98") (pinfunction "D17_98") (pintype "bidirectional"))
    )
    (net (code "88") (name "unconnected-(IC1-D18-Pad88)") (class "Default")
      (node (ref "IC1") (pin "88") (pinfunction "D18_88") (pintype "bidirectional"))
    )
    (net (code "89") (name "unconnected-(IC1-D19-Pad87)") (class "Default")
      (node (ref "IC1") (pin "87") (pinfunction "D19_87") (pintype "bidirectional"))
    )
    (net (code "90") (name "unconnected-(IC1-D20-Pad92)") (class "Default")
      (node (ref "IC1") (pin "92") (pinfunction "D20_92") (pintype "bidirectional"))
    )
    (net (code "91") (name "unconnected-(IC1-D21-Pad91)") (class "Default")
      (node (ref "IC1") (pin "91") (pinfunction "D21_91") (pintype "bidirectional"))
    )
    (net (code "92") (name "unconnected-(IC1-D22-Pad90)") (class "Default")
      (node (ref "IC1") (pin "90") (pinfunction "D22_90") (pintype "bidirectional"))
    )
    (net (code "93") (name "unconnected-(IC1-D23-Pad89)") (class "Default")
      (node (ref "IC1") (pin "89") (pinfunction "D23_89") (pintype "bidirectional"))
    )
    (net (code "94") (name "unconnected-(IC1-GAMAS0-Pad52)") (class "Default")
      (node (ref "IC1") (pin "52") (pinfunction "GAMAS0_52") (pintype "bidirectional"))
    )
    (net (code "95") (name "unconnected-(IC1-GAMAS1-Pad53)") (class "Default")
      (node (ref "IC1") (pin "53") (pinfunction "GAMAS1_53") (pintype "bidirectional"))
    )
    (net (code "96") (name "unconnected-(IC1-GPIO3-Pad39)") (class "Default")
      (node (ref "IC1") (pin "39") (pinfunction "GPIO3_39") (pintype "bidirectional"))
    )
    (net (code "97") (name "unconnected-(IC1-LDATA18-Pad86)") (class "Default")
      (node (ref "IC1") (pin "86") (pinfunction "LDATA18_86") (pintype "bidirectional"))
    )
    (net (code "98") (name "unconnected-(IC1-LDATA19-Pad85)") (class "Default")
      (node (ref "IC1") (pin "85") (pinfunction "LDATA19_85") (pintype "bidirectional"))
    )
    (net (code "99") (name "unconnected-(IC1-LDATA20-Pad31)") (class "Default")
      (node (ref "IC1") (pin "31") (pinfunction "LDATA20_31") (pintype "bidirectional"))
    )
    (net (code "100") (name "unconnected-(IC1-LDATA21-Pad30)") (class "Default")
      (node (ref "IC1") (pin "30") (pinfunction "LDATA21_30") (pintype "bidirectional"))
    )
    (net (code "101") (name "unconnected-(IC1-LDATA22-Pad29)") (class "Default")
      (node (ref "IC1") (pin "29") (pinfunction "LDATA22_29") (pintype "bidirectional"))
    )
    (net (code "102") (name "unconnected-(IC1-LDATA23-Pad28)") (class "Default")
      (node (ref "IC1") (pin "28") (pinfunction "LDATA23_28") (pintype "bidirectional"))
    )
    (net (code "103") (name "unconnected-(IC4-AUX-Pad8)") (class "Default")
      (node (ref "IC4") (pin "8") (pinfunction "AUX_8") (pintype "bidirectional"))
    )
    (net (code "104") (name "unconnected-(IC4-BUSY-Pad13)") (class "Default")
      (node (ref "IC4") (pin "13") (pinfunction "BUSY_13") (pintype "bidirectional"))
    )
    (net (code "105") (name "unconnected-(IC4-VBAT-Pad7)") (class "Default")
      (node (ref "IC4") (pin "7") (pinfunction "VBAT_7") (pintype "bidirectional"))
    )
    (net (code "106") (name "unconnected-(J1-Pad5)") (class "Default")
      (node (ref "J1") (pin "5") (pinfunction "5_5") (pintype "passive"))
    )
    (net (code "107") (name "unconnected-(J1-Pad24)") (class "Default")
      (node (ref "J1") (pin "24") (pinfunction "24_24") (pintype "passive"))
    )
    (net (code "108") (name "unconnected-(J1-Pad38)") (class "Default")
      (node (ref "J1") (pin "38") (pinfunction "38_38") (pintype "passive"))
    )
    (net (code "109") (name "unconnected-(J1-Pad39)") (class "Default")
      (node (ref "J1") (pin "39") (pinfunction "39_39") (pintype "passive"))
    )
    (net (code "110") (name "unconnected-(J1-Pad40)") (class "Default")
      (node (ref "J1") (pin "40") (pinfunction "40_40") (pintype "passive"))
    )
    (net (code "111") (name "unconnected-(SOC_1-CDI#-Pad11)") (class "Default")
      (node (ref "SOC_1") (pin "11") (pinfunction "CDI#_11") (pintype "output"))
    )
    (net (code "112") (name "unconnected-(SOC_1-DAT1-Pad8)") (class "Default")
      (node (ref "SOC_1") (pin "8") (pinfunction "DAT1_8") (pintype "bidirectional"))
    )
    (net (code "113") (name "unconnected-(SOC_1-DAT2-Pad9)") (class "Default")
      (node (ref "SOC_1") (pin "9") (pinfunction "DAT2_9") (pintype "bidirectional"))
    )
    (net (code "114") (name "unconnected-(SOC_1-WP-Pad10)") (class "Default")
      (node (ref "SOC_1") (pin "10") (pinfunction "WP_10") (pintype "output"))
    )
    (net (code "115") (name "unconnected-(TFT1-Pad1)") (class "Default")
      (node (ref "TFT1") (pin "1") (pinfunction "1_1") (pintype "passive"))
    )
    (net (code "116") (name "unconnected-(TFT1AU-1-Pad6)") (class "Default")
      (node (ref "TFT1") (pin "6") (pinfunction "1_6") (pintype "passive"))
    )
    (net (code "117") (name "unconnected-(TFT1L-1-Pad2)") (class "Default")
      (node (ref "TFT1") (pin "2") (pinfunction "1_2") (pintype "passive"))
    )
  )
)
